# Sheet5.net
KiCad netlist of a schematic drawn in Altium Designer
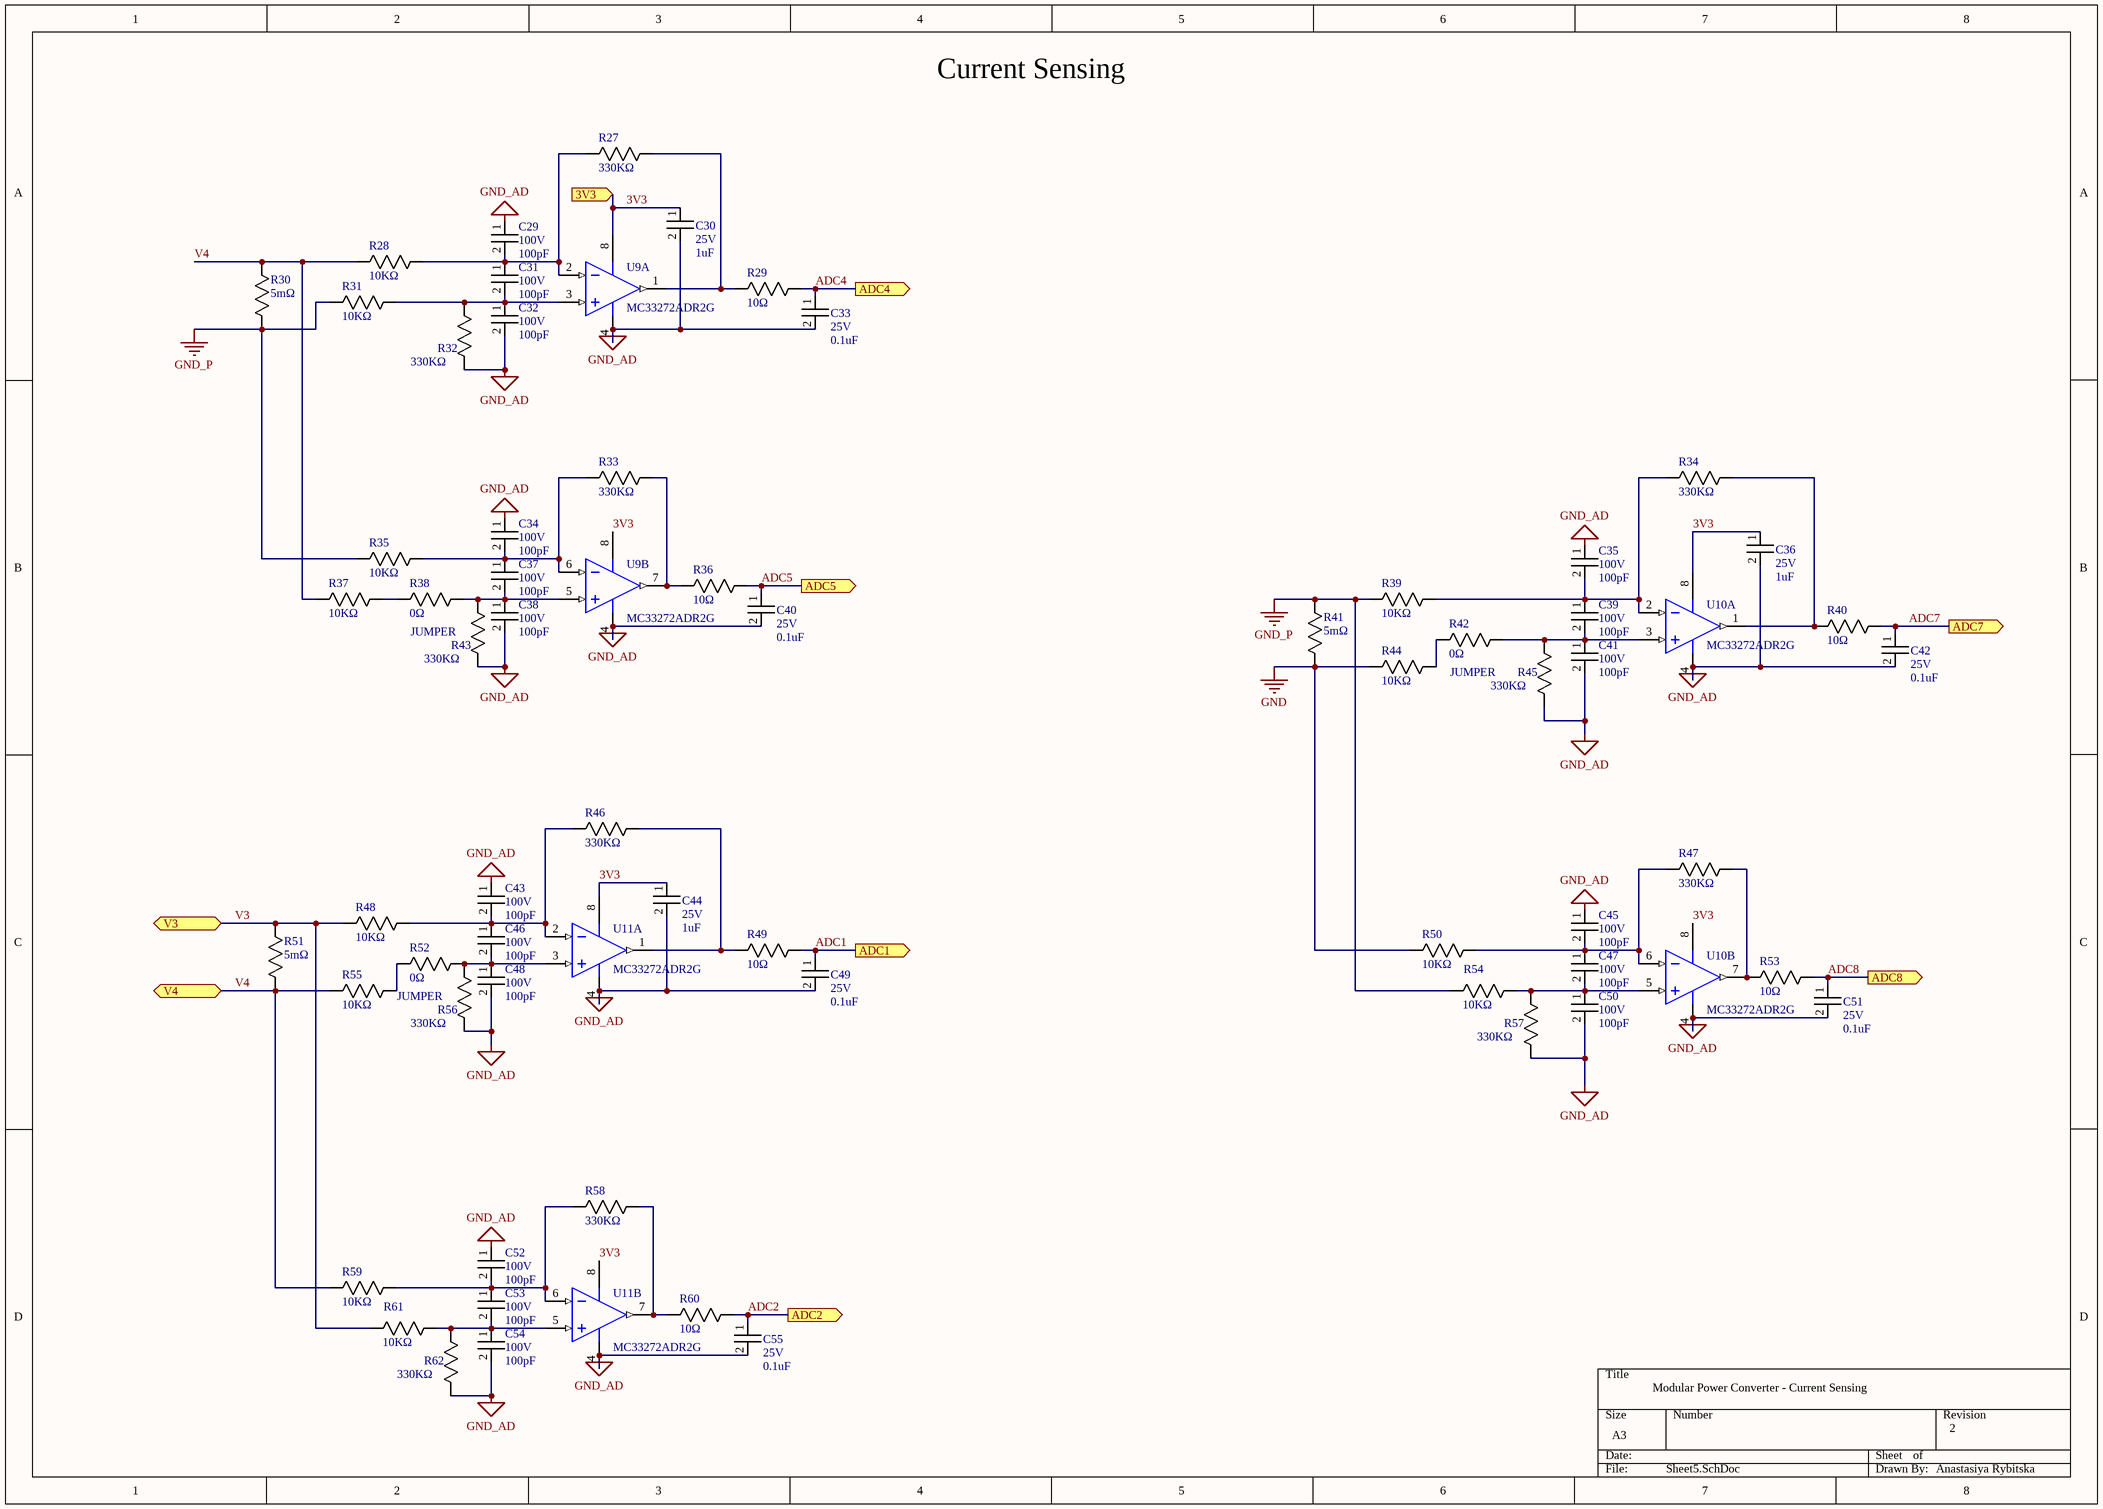
[diagram p0: Sheet5.SchDoc]

(export (version "E")
  (design (tool "Eeschema 10.0.6"))
  (components
    (comp (ref "C29")
      (value "06031C101KAT2A")
      (footprint "0603")
      (fields (field (name "VOLTAGE RATING") "100V") (field (name "CAPACITANCE") "100pF"))
      (libsource (lib "Schlib1") (part "06031C101KAT2A"))
    )
    (comp (ref "C30")
      (value "CL10B105KA8NFNC")
      (footprint "0603")
      (description "Cap Ceramic 1uF 25V X7R ±10% Pad SMD 0603 +125°C T/R")
      (fields (field (name "VOLTAGE RATING") "25V") (field (name "CAPACITANCE") "1uF"))
      (libsource (lib "Schlib1") (part "CL10B105KA8NFNC"))
    )
    (comp (ref "C31")
      (value "06031C101KAT2A")
      (footprint "0603")
      (fields (field (name "VOLTAGE RATING") "100V") (field (name "CAPACITANCE") "100pF"))
      (libsource (lib "Schlib1") (part "06031C101KAT2A"))
    )
    (comp (ref "C32")
      (value "06031C101KAT2A")
      (footprint "0603")
      (fields (field (name "VOLTAGE RATING") "100V") (field (name "CAPACITANCE") "100pF"))
      (libsource (lib "Schlib1") (part "06031C101KAT2A"))
    )
    (comp (ref "C33")
      (value "CC0603MRX7R8BB104")
      (footprint "0603")
      (description "CAP CER 0.1UF 25V X7R 0603")
      (fields (field (name "VOLTAGE RATING") "25V") (field (name "CAPACITANCE") "0.1uF"))
      (libsource (lib "Schlib1") (part "CC0603MRX7R8BB104"))
    )
    (comp (ref "C34")
      (value "06031C101KAT2A")
      (footprint "0603")
      (fields (field (name "VOLTAGE RATING") "100V") (field (name "CAPACITANCE") "100pF"))
      (libsource (lib "Schlib1") (part "06031C101KAT2A"))
    )
    (comp (ref "C35")
      (value "06031C101KAT2A")
      (footprint "0603")
      (fields (field (name "VOLTAGE RATING") "100V") (field (name "CAPACITANCE") "100pF"))
      (libsource (lib "Schlib1") (part "06031C101KAT2A"))
    )
    (comp (ref "C36")
      (value "CL10B105KA8NFNC")
      (footprint "0603")
      (description "Cap Ceramic 1uF 25V X7R ±10% Pad SMD 0603 +125°C T/R")
      (fields (field (name "VOLTAGE RATING") "25V") (field (name "CAPACITANCE") "1uF"))
      (libsource (lib "Schlib1") (part "CL10B105KA8NFNC"))
    )
    (comp (ref "C37")
      (value "06031C101KAT2A")
      (footprint "0603")
      (fields (field (name "VOLTAGE RATING") "100V") (field (name "CAPACITANCE") "100pF"))
      (libsource (lib "Schlib1") (part "06031C101KAT2A"))
    )
    (comp (ref "C38")
      (value "06031C101KAT2A")
      (footprint "0603")
      (fields (field (name "VOLTAGE RATING") "100V") (field (name "CAPACITANCE") "100pF"))
      (libsource (lib "Schlib1") (part "06031C101KAT2A"))
    )
    (comp (ref "C39")
      (value "06031C101KAT2A")
      (footprint "0603")
      (fields (field (name "VOLTAGE RATING") "100V") (field (name "CAPACITANCE") "100pF"))
      (libsource (lib "Schlib1") (part "06031C101KAT2A"))
    )
    (comp (ref "C40")
      (value "CC0603MRX7R8BB104")
      (footprint "0603")
      (description "CAP CER 0.1UF 25V X7R 0603")
      (fields (field (name "VOLTAGE RATING") "25V") (field (name "CAPACITANCE") "0.1uF"))
      (libsource (lib "Schlib1") (part "CC0603MRX7R8BB104"))
    )
    (comp (ref "C41")
      (value "06031C101KAT2A")
      (footprint "0603")
      (fields (field (name "VOLTAGE RATING") "100V") (field (name "CAPACITANCE") "100pF"))
      (libsource (lib "Schlib1") (part "06031C101KAT2A"))
    )
    (comp (ref "C42")
      (value "CC0603MRX7R8BB104")
      (footprint "0603")
      (description "CAP CER 0.1UF 25V X7R 0603")
      (fields (field (name "VOLTAGE RATING") "25V") (field (name "CAPACITANCE") "0.1uF"))
      (libsource (lib "Schlib1") (part "CC0603MRX7R8BB104"))
    )
    (comp (ref "C43")
      (value "06031C101KAT2A")
      (footprint "0603")
      (fields (field (name "VOLTAGE RATING") "100V") (field (name "CAPACITANCE") "100pF"))
      (libsource (lib "Schlib1") (part "06031C101KAT2A"))
    )
    (comp (ref "C44")
      (value "CL10B105KA8NFNC")
      (footprint "0603")
      (description "Cap Ceramic 1uF 25V X7R ±10% Pad SMD 0603 +125°C T/R")
      (fields (field (name "VOLTAGE RATING") "25V") (field (name "CAPACITANCE") "1uF"))
      (libsource (lib "Schlib1") (part "CL10B105KA8NFNC"))
    )
    (comp (ref "C45")
      (value "06031C101KAT2A")
      (footprint "0603")
      (fields (field (name "VOLTAGE RATING") "100V") (field (name "CAPACITANCE") "100pF"))
      (libsource (lib "Schlib1") (part "06031C101KAT2A"))
    )
    (comp (ref "C46")
      (value "06031C101KAT2A")
      (footprint "0603")
      (fields (field (name "VOLTAGE RATING") "100V") (field (name "CAPACITANCE") "100pF"))
      (libsource (lib "Schlib1") (part "06031C101KAT2A"))
    )
    (comp (ref "C47")
      (value "06031C101KAT2A")
      (footprint "0603")
      (fields (field (name "VOLTAGE RATING") "100V") (field (name "CAPACITANCE") "100pF"))
      (libsource (lib "Schlib1") (part "06031C101KAT2A"))
    )
    (comp (ref "C48")
      (value "06031C101KAT2A")
      (footprint "0603")
      (fields (field (name "VOLTAGE RATING") "100V") (field (name "CAPACITANCE") "100pF"))
      (libsource (lib "Schlib1") (part "06031C101KAT2A"))
    )
    (comp (ref "C49")
      (value "CC0603MRX7R8BB104")
      (footprint "0603")
      (description "CAP CER 0.1UF 25V X7R 0603")
      (fields (field (name "VOLTAGE RATING") "25V") (field (name "CAPACITANCE") "0.1uF"))
      (libsource (lib "Schlib1") (part "CC0603MRX7R8BB104"))
    )
    (comp (ref "C50")
      (value "06031C101KAT2A")
      (footprint "0603")
      (fields (field (name "VOLTAGE RATING") "100V") (field (name "CAPACITANCE") "100pF"))
      (libsource (lib "Schlib1") (part "06031C101KAT2A"))
    )
    (comp (ref "C51")
      (value "CC0603MRX7R8BB104")
      (footprint "0603")
      (description "CAP CER 0.1UF 25V X7R 0603")
      (fields (field (name "VOLTAGE RATING") "25V") (field (name "CAPACITANCE") "0.1uF"))
      (libsource (lib "Schlib1") (part "CC0603MRX7R8BB104"))
    )
    (comp (ref "C52")
      (value "06031C101KAT2A")
      (footprint "0603")
      (fields (field (name "VOLTAGE RATING") "100V") (field (name "CAPACITANCE") "100pF"))
      (libsource (lib "Schlib1") (part "06031C101KAT2A"))
    )
    (comp (ref "C53")
      (value "06031C101KAT2A")
      (footprint "0603")
      (fields (field (name "VOLTAGE RATING") "100V") (field (name "CAPACITANCE") "100pF"))
      (libsource (lib "Schlib1") (part "06031C101KAT2A"))
    )
    (comp (ref "C54")
      (value "06031C101KAT2A")
      (footprint "0603")
      (fields (field (name "VOLTAGE RATING") "100V") (field (name "CAPACITANCE") "100pF"))
      (libsource (lib "Schlib1") (part "06031C101KAT2A"))
    )
    (comp (ref "C55")
      (value "CC0603MRX7R8BB104")
      (footprint "0603")
      (description "CAP CER 0.1UF 25V X7R 0603")
      (fields (field (name "VOLTAGE RATING") "25V") (field (name "CAPACITANCE") "0.1uF"))
      (libsource (lib "Schlib1") (part "CC0603MRX7R8BB104"))
    )
    (comp (ref "R27")
      (value "ERJ3EKF3303V")
      (footprint "0603")
      (fields (field (name "RESISTANCE") "330KΩ"))
      (libsource (lib "Schlib1") (part "ERJ3EKF3303V"))
    )
    (comp (ref "R28")
      (value "RNCP0603FTD10K0")
      (footprint "0603")
      (description "10kΩ ±1% 0.125W 0603 High Power Anti-Sulfur Thin Film Chip Resistor")
      (fields (field (name "RESISTANCE") "10KΩ"))
      (libsource (lib "Schlib1") (part "RNCP0603FTD10K0"))
    )
    (comp (ref "R29")
      (value "RMCF0603JT10R0")
      (footprint "0603")
      (description "RES 10 OHM 5% 1/10W 0603")
      (fields (field (name "RESISTANCE") "10Ω"))
      (libsource (lib "Schlib1") (part "RMCF0603JT10R0"))
    )
    (comp (ref "R30")
      (value "LVT12R0050FER")
      (footprint "RES_LVT12_004-020_OHM")
      (description "No Description Available")
      (fields
        (field (name "RESISTANCE") "5mΩ")
        (field (name "COPYRIGHT") "Copyright (C) 2022 Ultra Librarian. All rights reserved.")
      )
      (libsource (lib "LVT12R0050FER") (part "LVT12R0050FER"))
    )
    (comp (ref "R31")
      (value "RNCP0603FTD10K0")
      (footprint "0603")
      (description "10kΩ ±1% 0.125W 0603 High Power Anti-Sulfur Thin Film Chip Resistor")
      (fields (field (name "RESISTANCE") "10KΩ"))
      (libsource (lib "Schlib1") (part "RNCP0603FTD10K0"))
    )
    (comp (ref "R32")
      (value "ERJ3EKF3303V")
      (footprint "0603")
      (fields (field (name "RESISTANCE") "330KΩ"))
      (libsource (lib "Schlib1") (part "ERJ3EKF3303V"))
    )
    (comp (ref "R33")
      (value "ERJ3EKF3303V")
      (footprint "0603")
      (fields (field (name "RESISTANCE") "330KΩ"))
      (libsource (lib "Schlib1") (part "ERJ3EKF3303V"))
    )
    (comp (ref "R34")
      (value "ERJ3EKF3303V")
      (footprint "0603")
      (fields (field (name "RESISTANCE") "330KΩ"))
      (libsource (lib "Schlib1") (part "ERJ3EKF3303V"))
    )
    (comp (ref "R35")
      (value "RNCP0603FTD10K0")
      (footprint "0603")
      (description "10kΩ ±1% 0.125W 0603 High Power Anti-Sulfur Thin Film Chip Resistor")
      (fields (field (name "RESISTANCE") "10KΩ"))
      (libsource (lib "Schlib1") (part "RNCP0603FTD10K0"))
    )
    (comp (ref "R36")
      (value "RMCF0603JT10R0")
      (footprint "0603")
      (description "RES 10 OHM 5% 1/10W 0603")
      (fields (field (name "RESISTANCE") "10Ω"))
      (libsource (lib "Schlib1") (part "RMCF0603JT10R0"))
    )
    (comp (ref "R37")
      (value "RNCP0603FTD10K0")
      (footprint "0603")
      (description "10kΩ ±1% 0.125W 0603 High Power Anti-Sulfur Thin Film Chip Resistor")
      (fields (field (name "RESISTANCE") "10KΩ"))
      (libsource (lib "Schlib1") (part "RNCP0603FTD10K0"))
    )
    (comp (ref "R38")
      (value "AC0603FR-070RL")
      (footprint "0603")
      (description "RES SMD 0 OHM JUMPER 1/10W 0603")
      (fields (field (name "RESISTANCE") "0Ω"))
      (libsource (lib "Schlib1") (part "AC0603FR-070RL"))
    )
    (comp (ref "R39")
      (value "RNCP0603FTD10K0")
      (footprint "0603")
      (description "10kΩ ±1% 0.125W 0603 High Power Anti-Sulfur Thin Film Chip Resistor")
      (fields (field (name "RESISTANCE") "10KΩ"))
      (libsource (lib "Schlib1") (part "RNCP0603FTD10K0"))
    )
    (comp (ref "R40")
      (value "RMCF0603JT10R0")
      (footprint "0603")
      (description "RES 10 OHM 5% 1/10W 0603")
      (fields (field (name "RESISTANCE") "10Ω"))
      (libsource (lib "Schlib1") (part "RMCF0603JT10R0"))
    )
    (comp (ref "R41")
      (value "LVT12R0050FER")
      (footprint "RES_LVT12_004-020_OHM")
      (description "No Description Available")
      (fields
        (field (name "RESISTANCE") "5mΩ")
        (field (name "COPYRIGHT") "Copyright (C) 2022 Ultra Librarian. All rights reserved.")
      )
      (libsource (lib "LVT12R0050FER") (part "LVT12R0050FER"))
    )
    (comp (ref "R42")
      (value "AC0603FR-070RL")
      (footprint "0603")
      (description "RES SMD 0 OHM JUMPER 1/10W 0603")
      (fields (field (name "RESISTANCE") "0Ω"))
      (libsource (lib "Schlib1") (part "AC0603FR-070RL"))
    )
    (comp (ref "R43")
      (value "ERJ3EKF3303V")
      (footprint "0603")
      (fields (field (name "RESISTANCE") "330KΩ"))
      (libsource (lib "Schlib1") (part "ERJ3EKF3303V"))
    )
    (comp (ref "R44")
      (value "RNCP0603FTD10K0")
      (footprint "0603")
      (description "10kΩ ±1% 0.125W 0603 High Power Anti-Sulfur Thin Film Chip Resistor")
      (fields (field (name "RESISTANCE") "10KΩ"))
      (libsource (lib "Schlib1") (part "RNCP0603FTD10K0"))
    )
    (comp (ref "R45")
      (value "ERJ3EKF3303V")
      (footprint "0603")
      (fields (field (name "RESISTANCE") "330KΩ"))
      (libsource (lib "Schlib1") (part "ERJ3EKF3303V"))
    )
    (comp (ref "R46")
      (value "ERJ3EKF3303V")
      (footprint "0603")
      (fields (field (name "RESISTANCE") "330KΩ"))
      (libsource (lib "Schlib1") (part "ERJ3EKF3303V"))
    )
    (comp (ref "R47")
      (value "ERJ3EKF3303V")
      (footprint "0603")
      (fields (field (name "RESISTANCE") "330KΩ"))
      (libsource (lib "Schlib1") (part "ERJ3EKF3303V"))
    )
    (comp (ref "R48")
      (value "RNCP0603FTD10K0")
      (footprint "0603")
      (description "10kΩ ±1% 0.125W 0603 High Power Anti-Sulfur Thin Film Chip Resistor")
      (fields (field (name "RESISTANCE") "10KΩ"))
      (libsource (lib "Schlib1") (part "RNCP0603FTD10K0"))
    )
    (comp (ref "R49")
      (value "RMCF0603JT10R0")
      (footprint "0603")
      (description "RES 10 OHM 5% 1/10W 0603")
      (fields (field (name "RESISTANCE") "10Ω"))
      (libsource (lib "Schlib1") (part "RMCF0603JT10R0"))
    )
    (comp (ref "R50")
      (value "RNCP0603FTD10K0")
      (footprint "0603")
      (description "10kΩ ±1% 0.125W 0603 High Power Anti-Sulfur Thin Film Chip Resistor")
      (fields (field (name "RESISTANCE") "10KΩ"))
      (libsource (lib "Schlib1") (part "RNCP0603FTD10K0"))
    )
    (comp (ref "R51")
      (value "LVT12R0050FER")
      (footprint "RES_LVT12_004-020_OHM")
      (description "No Description Available")
      (fields
        (field (name "RESISTANCE") "5mΩ")
        (field (name "COPYRIGHT") "Copyright (C) 2022 Ultra Librarian. All rights reserved.")
      )
      (libsource (lib "LVT12R0050FER") (part "LVT12R0050FER"))
    )
    (comp (ref "R52")
      (value "AC0603FR-070RL")
      (footprint "0603")
      (description "RES SMD 0 OHM JUMPER 1/10W 0603")
      (fields (field (name "RESISTANCE") "0Ω"))
      (libsource (lib "Schlib1") (part "AC0603FR-070RL"))
    )
    (comp (ref "R53")
      (value "RMCF0603JT10R0")
      (footprint "0603")
      (description "RES 10 OHM 5% 1/10W 0603")
      (fields (field (name "RESISTANCE") "10Ω"))
      (libsource (lib "Schlib1") (part "RMCF0603JT10R0"))
    )
    (comp (ref "R54")
      (value "RNCP0603FTD10K0")
      (footprint "0603")
      (description "10kΩ ±1% 0.125W 0603 High Power Anti-Sulfur Thin Film Chip Resistor")
      (fields (field (name "RESISTANCE") "10KΩ"))
      (libsource (lib "Schlib1") (part "RNCP0603FTD10K0"))
    )
    (comp (ref "R55")
      (value "RNCP0603FTD10K0")
      (footprint "0603")
      (description "10kΩ ±1% 0.125W 0603 High Power Anti-Sulfur Thin Film Chip Resistor")
      (fields (field (name "RESISTANCE") "10KΩ"))
      (libsource (lib "Schlib1") (part "RNCP0603FTD10K0"))
    )
    (comp (ref "R56")
      (value "ERJ3EKF3303V")
      (footprint "0603")
      (fields (field (name "RESISTANCE") "330KΩ"))
      (libsource (lib "Schlib1") (part "ERJ3EKF3303V"))
    )
    (comp (ref "R57")
      (value "ERJ3EKF3303V")
      (footprint "0603")
      (fields (field (name "RESISTANCE") "330KΩ"))
      (libsource (lib "Schlib1") (part "ERJ3EKF3303V"))
    )
    (comp (ref "R58")
      (value "ERJ3EKF3303V")
      (footprint "0603")
      (fields (field (name "RESISTANCE") "330KΩ"))
      (libsource (lib "Schlib1") (part "ERJ3EKF3303V"))
    )
    (comp (ref "R59")
      (value "RNCP0603FTD10K0")
      (footprint "0603")
      (description "10kΩ ±1% 0.125W 0603 High Power Anti-Sulfur Thin Film Chip Resistor")
      (fields (field (name "RESISTANCE") "10KΩ"))
      (libsource (lib "Schlib1") (part "RNCP0603FTD10K0"))
    )
    (comp (ref "R60")
      (value "RMCF0603JT10R0")
      (footprint "0603")
      (description "RES 10 OHM 5% 1/10W 0603")
      (fields (field (name "RESISTANCE") "10Ω"))
      (libsource (lib "Schlib1") (part "RMCF0603JT10R0"))
    )
    (comp (ref "R61")
      (value "RNCP0603FTD10K0")
      (footprint "0603")
      (description "10kΩ ±1% 0.125W 0603 High Power Anti-Sulfur Thin Film Chip Resistor")
      (fields (field (name "RESISTANCE") "10KΩ"))
      (libsource (lib "Schlib1") (part "RNCP0603FTD10K0"))
    )
    (comp (ref "R62")
      (value "ERJ3EKF3303V")
      (footprint "0603")
      (fields (field (name "RESISTANCE") "330KΩ"))
      (libsource (lib "Schlib1") (part "ERJ3EKF3303V"))
    )
    (comp (ref "U9")
      (value "MC33272ADR2G")
      (footprint "ONSC-SOIC-8-751-07_V")
      (fields (field (name "MANUFACTURER") "On Semiconductor"))
      (libsource (lib "Altium Content Vault") (part "ONSC-LM833_MC3XXXXX_NCV33202-8"))
    )
    (comp (ref "U10")
      (value "MC33272ADR2G")
      (footprint "ONSC-SOIC-8-751-07_V")
      (fields (field (name "MANUFACTURER") "On Semiconductor"))
      (libsource (lib "Altium Content Vault") (part "ONSC-LM833_MC3XXXXX_NCV33202-8"))
    )
    (comp (ref "U11")
      (value "MC33272ADR2G")
      (footprint "ONSC-SOIC-8-751-07_V")
      (fields (field (name "MANUFACTURER") "On Semiconductor"))
      (libsource (lib "Altium Content Vault") (part "ONSC-LM833_MC3XXXXX_NCV33202-8"))
    )
  )
  (nets
    (net (code "1") (name "/3V3") (class "Default")
      (node (ref "C30") (pin "1") (pinfunction "1_1") (pintype "passive"))
      (node (ref "C36") (pin "1") (pinfunction "1_1") (pintype "passive"))
      (node (ref "C44") (pin "1") (pinfunction "1_1") (pintype "passive"))
      (node (ref "U10") (pin "8") (pinfunction "VCC_8") (pintype "passive"))
      (node (ref "U11") (pin "8") (pinfunction "VCC_8") (pintype "passive"))
      (node (ref "U9") (pin "8") (pinfunction "VCC_8") (pintype "passive"))
    )
    (net (code "2") (name "/ADC1") (class "Default")
      (node (ref "C49") (pin "1") (pinfunction "1_1") (pintype "passive"))
      (node (ref "R49") (pin "2") (pinfunction "2_2") (pintype "passive"))
    )
    (net (code "3") (name "/ADC2") (class "Default")
      (node (ref "C55") (pin "1") (pinfunction "1_1") (pintype "passive"))
      (node (ref "R60") (pin "2") (pinfunction "2_2") (pintype "passive"))
    )
    (net (code "4") (name "/ADC4") (class "Default")
      (node (ref "C33") (pin "1") (pinfunction "1_1") (pintype "passive"))
      (node (ref "R29") (pin "2") (pinfunction "2_2") (pintype "passive"))
    )
    (net (code "5") (name "/ADC5") (class "Default")
      (node (ref "C40") (pin "1") (pinfunction "1_1") (pintype "passive"))
      (node (ref "R36") (pin "2") (pinfunction "2_2") (pintype "passive"))
    )
    (net (code "6") (name "/ADC7") (class "Default")
      (node (ref "C42") (pin "1") (pinfunction "1_1") (pintype "passive"))
      (node (ref "R40") (pin "2") (pinfunction "2_2") (pintype "passive"))
    )
    (net (code "7") (name "/ADC8") (class "Default")
      (node (ref "C51") (pin "1") (pinfunction "1_1") (pintype "passive"))
      (node (ref "R53") (pin "2") (pinfunction "2_2") (pintype "passive"))
    )
    (net (code "8") (name "/V3") (class "Default")
      (node (ref "R48") (pin "1") (pinfunction "1_1") (pintype "passive"))
      (node (ref "R51") (pin "2") (pinfunction "2_2") (pintype "passive"))
      (node (ref "R61") (pin "1") (pinfunction "1_1") (pintype "passive"))
    )
    (net (code "9") (name "/V4") (class "Default")
      (node (ref "R28") (pin "1") (pinfunction "1_1") (pintype "passive"))
      (node (ref "R30") (pin "2") (pinfunction "2_2") (pintype "passive"))
      (node (ref "R37") (pin "1") (pinfunction "1_1") (pintype "passive"))
      (node (ref "R51") (pin "1") (pinfunction "1_1") (pintype "passive"))
      (node (ref "R55") (pin "1") (pinfunction "1_1") (pintype "passive"))
      (node (ref "R59") (pin "1") (pinfunction "1_1") (pintype "passive"))
    )
    (net (code "10") (name "GND") (class "Default")
      (node (ref "R41") (pin "1") (pinfunction "1_1") (pintype "passive"))
      (node (ref "R44") (pin "1") (pinfunction "1_1") (pintype "passive"))
      (node (ref "R50") (pin "1") (pinfunction "1_1") (pintype "passive"))
    )
    (net (code "11") (name "GND_AD") (class "Default")
      (node (ref "C29") (pin "1") (pinfunction "1_1") (pintype "passive"))
      (node (ref "C30") (pin "2") (pinfunction "2_2") (pintype "passive"))
      (node (ref "C32") (pin "2") (pinfunction "2_2") (pintype "passive"))
      (node (ref "C33") (pin "2") (pinfunction "2_2") (pintype "passive"))
      (node (ref "C34") (pin "1") (pinfunction "1_1") (pintype "passive"))
      (node (ref "C35") (pin "1") (pinfunction "1_1") (pintype "passive"))
      (node (ref "C36") (pin "2") (pinfunction "2_2") (pintype "passive"))
      (node (ref "C38") (pin "2") (pinfunction "2_2") (pintype "passive"))
      (node (ref "C40") (pin "2") (pinfunction "2_2") (pintype "passive"))
      (node (ref "C41") (pin "2") (pinfunction "2_2") (pintype "passive"))
      (node (ref "C42") (pin "2") (pinfunction "2_2") (pintype "passive"))
      (node (ref "C43") (pin "1") (pinfunction "1_1") (pintype "passive"))
      (node (ref "C44") (pin "2") (pinfunction "2_2") (pintype "passive"))
      (node (ref "C45") (pin "1") (pinfunction "1_1") (pintype "passive"))
      (node (ref "C48") (pin "2") (pinfunction "2_2") (pintype "passive"))
      (node (ref "C49") (pin "2") (pinfunction "2_2") (pintype "passive"))
      (node (ref "C50") (pin "2") (pinfunction "2_2") (pintype "passive"))
      (node (ref "C51") (pin "2") (pinfunction "2_2") (pintype "passive"))
      (node (ref "C52") (pin "1") (pinfunction "1_1") (pintype "passive"))
      (node (ref "C54") (pin "2") (pinfunction "2_2") (pintype "passive"))
      (node (ref "C55") (pin "2") (pinfunction "2_2") (pintype "passive"))
      (node (ref "R32") (pin "1") (pinfunction "1_1") (pintype "passive"))
      (node (ref "R43") (pin "1") (pinfunction "1_1") (pintype "passive"))
      (node (ref "R45") (pin "1") (pinfunction "1_1") (pintype "passive"))
      (node (ref "R56") (pin "1") (pinfunction "1_1") (pintype "passive"))
      (node (ref "R57") (pin "1") (pinfunction "1_1") (pintype "passive"))
      (node (ref "R62") (pin "1") (pinfunction "1_1") (pintype "passive"))
      (node (ref "U10") (pin "4") (pinfunction "VEE_4") (pintype "power_in"))
      (node (ref "U11") (pin "4") (pinfunction "VEE_4") (pintype "power_in"))
      (node (ref "U9") (pin "4") (pinfunction "VEE_4") (pintype "power_in"))
    )
    (net (code "12") (name "GND_P") (class "Default")
      (node (ref "R30") (pin "1") (pinfunction "1_1") (pintype "passive"))
      (node (ref "R31") (pin "1") (pinfunction "1_1") (pintype "passive"))
      (node (ref "R35") (pin "1") (pinfunction "1_1") (pintype "passive"))
      (node (ref "R39") (pin "1") (pinfunction "1_1") (pintype "passive"))
      (node (ref "R41") (pin "2") (pinfunction "2_2") (pintype "passive"))
      (node (ref "R54") (pin "1") (pinfunction "1_1") (pintype "passive"))
    )
    (net (code "13") (name "Net-(R37-Pad2)") (class "Default")
      (node (ref "R37") (pin "2") (pinfunction "2_2") (pintype "passive"))
      (node (ref "R38") (pin "1") (pinfunction "1_1") (pintype "passive"))
    )
    (net (code "14") (name "Net-(R42-Pad1)") (class "Default")
      (node (ref "R42") (pin "1") (pinfunction "1_1") (pintype "passive"))
      (node (ref "R44") (pin "2") (pinfunction "2_2") (pintype "passive"))
    )
    (net (code "15") (name "Net-(R52-Pad1)") (class "Default")
      (node (ref "R52") (pin "1") (pinfunction "1_1") (pintype "passive"))
      (node (ref "R55") (pin "2") (pinfunction "2_2") (pintype "passive"))
    )
    (net (code "16") (name "Net-(U9A-IN1+)") (class "Default")
      (node (ref "C31") (pin "2") (pinfunction "2_2") (pintype "passive"))
      (node (ref "C32") (pin "1") (pinfunction "1_1") (pintype "passive"))
      (node (ref "R31") (pin "2") (pinfunction "2_2") (pintype "passive"))
      (node (ref "R32") (pin "2") (pinfunction "2_2") (pintype "passive"))
      (node (ref "U9") (pin "3") (pinfunction "IN1+_3") (pintype "input"))
    )
    (net (code "17") (name "Net-(U9A-IN1-)") (class "Default")
      (node (ref "C29") (pin "2") (pinfunction "2_2") (pintype "passive"))
      (node (ref "C31") (pin "1") (pinfunction "1_1") (pintype "passive"))
      (node (ref "R27") (pin "1") (pinfunction "1_1") (pintype "passive"))
      (node (ref "R28") (pin "2") (pinfunction "2_2") (pintype "passive"))
      (node (ref "U9") (pin "2") (pinfunction "IN1-_2") (pintype "input"))
    )
    (net (code "18") (name "Net-(U9A-OUT1)") (class "Default")
      (node (ref "R27") (pin "2") (pinfunction "2_2") (pintype "passive"))
      (node (ref "R29") (pin "1") (pinfunction "1_1") (pintype "passive"))
      (node (ref "U9") (pin "1") (pinfunction "OUT1_1") (pintype "output"))
    )
    (net (code "19") (name "Net-(U9B-IN2+)") (class "Default")
      (node (ref "C37") (pin "2") (pinfunction "2_2") (pintype "passive"))
      (node (ref "C38") (pin "1") (pinfunction "1_1") (pintype "passive"))
      (node (ref "R38") (pin "2") (pinfunction "2_2") (pintype "passive"))
      (node (ref "R43") (pin "2") (pinfunction "2_2") (pintype "passive"))
      (node (ref "U9") (pin "5") (pinfunction "IN2+_5") (pintype "input"))
    )
    (net (code "20") (name "Net-(U9B-IN2-)") (class "Default")
      (node (ref "C34") (pin "2") (pinfunction "2_2") (pintype "passive"))
      (node (ref "C37") (pin "1") (pinfunction "1_1") (pintype "passive"))
      (node (ref "R33") (pin "1") (pinfunction "1_1") (pintype "passive"))
      (node (ref "R35") (pin "2") (pinfunction "2_2") (pintype "passive"))
      (node (ref "U9") (pin "6") (pinfunction "IN2-_6") (pintype "input"))
    )
    (net (code "21") (name "Net-(U9B-OUT2)") (class "Default")
      (node (ref "R33") (pin "2") (pinfunction "2_2") (pintype "passive"))
      (node (ref "R36") (pin "1") (pinfunction "1_1") (pintype "passive"))
      (node (ref "U9") (pin "7") (pinfunction "OUT2_7") (pintype "output"))
    )
    (net (code "22") (name "Net-(U10A-IN1+)") (class "Default")
      (node (ref "C39") (pin "2") (pinfunction "2_2") (pintype "passive"))
      (node (ref "C41") (pin "1") (pinfunction "1_1") (pintype "passive"))
      (node (ref "R42") (pin "2") (pinfunction "2_2") (pintype "passive"))
      (node (ref "R45") (pin "2") (pinfunction "2_2") (pintype "passive"))
      (node (ref "U10") (pin "3") (pinfunction "IN1+_3") (pintype "input"))
    )
    (net (code "23") (name "Net-(U10A-IN1-)") (class "Default")
      (node (ref "C35") (pin "2") (pinfunction "2_2") (pintype "passive"))
      (node (ref "C39") (pin "1") (pinfunction "1_1") (pintype "passive"))
      (node (ref "R34") (pin "1") (pinfunction "1_1") (pintype "passive"))
      (node (ref "R39") (pin "2") (pinfunction "2_2") (pintype "passive"))
      (node (ref "U10") (pin "2") (pinfunction "IN1-_2") (pintype "input"))
    )
    (net (code "24") (name "Net-(U10A-OUT1)") (class "Default")
      (node (ref "R34") (pin "2") (pinfunction "2_2") (pintype "passive"))
      (node (ref "R40") (pin "1") (pinfunction "1_1") (pintype "passive"))
      (node (ref "U10") (pin "1") (pinfunction "OUT1_1") (pintype "output"))
    )
    (net (code "25") (name "Net-(U10B-IN2+)") (class "Default")
      (node (ref "C47") (pin "2") (pinfunction "2_2") (pintype "passive"))
      (node (ref "C50") (pin "1") (pinfunction "1_1") (pintype "passive"))
      (node (ref "R54") (pin "2") (pinfunction "2_2") (pintype "passive"))
      (node (ref "R57") (pin "2") (pinfunction "2_2") (pintype "passive"))
      (node (ref "U10") (pin "5") (pinfunction "IN2+_5") (pintype "input"))
    )
    (net (code "26") (name "Net-(U10B-IN2-)") (class "Default")
      (node (ref "C45") (pin "2") (pinfunction "2_2") (pintype "passive"))
      (node (ref "C47") (pin "1") (pinfunction "1_1") (pintype "passive"))
      (node (ref "R47") (pin "1") (pinfunction "1_1") (pintype "passive"))
      (node (ref "R50") (pin "2") (pinfunction "2_2") (pintype "passive"))
      (node (ref "U10") (pin "6") (pinfunction "IN2-_6") (pintype "input"))
    )
    (net (code "27") (name "Net-(U10B-OUT2)") (class "Default")
      (node (ref "R47") (pin "2") (pinfunction "2_2") (pintype "passive"))
      (node (ref "R53") (pin "1") (pinfunction "1_1") (pintype "passive"))
      (node (ref "U10") (pin "7") (pinfunction "OUT2_7") (pintype "output"))
    )
    (net (code "28") (name "Net-(U11A-IN1+)") (class "Default")
      (node (ref "C46") (pin "2") (pinfunction "2_2") (pintype "passive"))
      (node (ref "C48") (pin "1") (pinfunction "1_1") (pintype "passive"))
      (node (ref "R52") (pin "2") (pinfunction "2_2") (pintype "passive"))
      (node (ref "R56") (pin "2") (pinfunction "2_2") (pintype "passive"))
      (node (ref "U11") (pin "3") (pinfunction "IN1+_3") (pintype "input"))
    )
    (net (code "29") (name "Net-(U11A-IN1-)") (class "Default")
      (node (ref "C43") (pin "2") (pinfunction "2_2") (pintype "passive"))
      (node (ref "C46") (pin "1") (pinfunction "1_1") (pintype "passive"))
      (node (ref "R46") (pin "1") (pinfunction "1_1") (pintype "passive"))
      (node (ref "R48") (pin "2") (pinfunction "2_2") (pintype "passive"))
      (node (ref "U11") (pin "2") (pinfunction "IN1-_2") (pintype "input"))
    )
    (net (code "30") (name "Net-(U11A-OUT1)") (class "Default")
      (node (ref "R46") (pin "2") (pinfunction "2_2") (pintype "passive"))
      (node (ref "R49") (pin "1") (pinfunction "1_1") (pintype "passive"))
      (node (ref "U11") (pin "1") (pinfunction "OUT1_1") (pintype "output"))
    )
    (net (code "31") (name "Net-(U11B-IN2+)") (class "Default")
      (node (ref "C53") (pin "2") (pinfunction "2_2") (pintype "passive"))
      (node (ref "C54") (pin "1") (pinfunction "1_1") (pintype "passive"))
      (node (ref "R61") (pin "2") (pinfunction "2_2") (pintype "passive"))
      (node (ref "R62") (pin "2") (pinfunction "2_2") (pintype "passive"))
      (node (ref "U11") (pin "5") (pinfunction "IN2+_5") (pintype "input"))
    )
    (net (code "32") (name "Net-(U11B-IN2-)") (class "Default")
      (node (ref "C52") (pin "2") (pinfunction "2_2") (pintype "passive"))
      (node (ref "C53") (pin "1") (pinfunction "1_1") (pintype "passive"))
      (node (ref "R58") (pin "1") (pinfunction "1_1") (pintype "passive"))
      (node (ref "R59") (pin "2") (pinfunction "2_2") (pintype "passive"))
      (node (ref "U11") (pin "6") (pinfunction "IN2-_6") (pintype "input"))
    )
    (net (code "33") (name "Net-(U11B-OUT2)") (class "Default")
      (node (ref "R58") (pin "2") (pinfunction "2_2") (pintype "passive"))
      (node (ref "R60") (pin "1") (pinfunction "1_1") (pintype "passive"))
      (node (ref "U11") (pin "7") (pinfunction "OUT2_7") (pintype "output"))
    )
  )
)
